# Blinds_Stepper.net
KiCad netlist of a schematic drawn in EAGLE
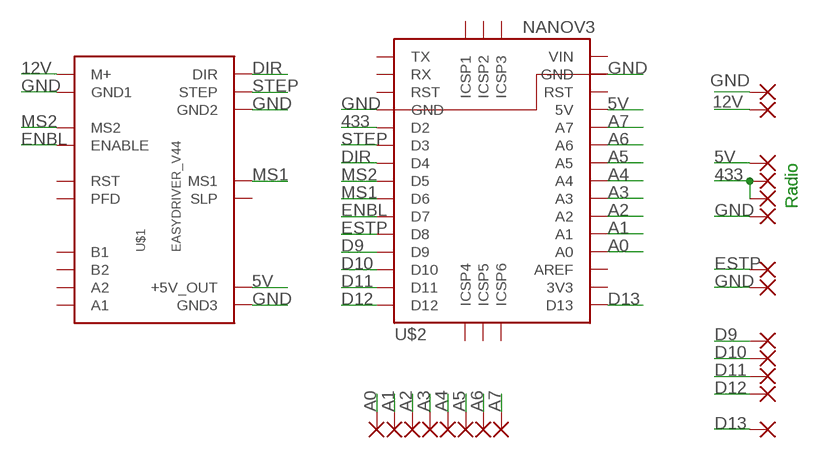
[diagram p0: schematic, sheet 1]

(export (version "E")
  (design (tool "Eeschema 10.0.6"))
  (components
    (comp (ref "+12")
      (value "1,6/0,8")
      (footprint "eagle-import:1,6_0,8")
      (libsource (lib "eagle-import") (part "1,6/0,8"))
    )
    (comp (ref "A0")
      (value "1,6/0,8")
      (footprint "eagle-import:1,6_0,8")
      (libsource (lib "eagle-import") (part "1,6/0,8"))
    )
    (comp (ref "A1")
      (value "1,6/0,8")
      (footprint "eagle-import:1,6_0,8")
      (libsource (lib "eagle-import") (part "1,6/0,8"))
    )
    (comp (ref "A2")
      (value "1,6/0,8")
      (footprint "eagle-import:1,6_0,8")
      (libsource (lib "eagle-import") (part "1,6/0,8"))
    )
    (comp (ref "A3")
      (value "1,6/0,8")
      (footprint "eagle-import:1,6_0,8")
      (libsource (lib "eagle-import") (part "1,6/0,8"))
    )
    (comp (ref "A4")
      (value "1,6/0,8")
      (footprint "eagle-import:1,6_0,8")
      (libsource (lib "eagle-import") (part "1,6/0,8"))
    )
    (comp (ref "A5")
      (value "1,6/0,8")
      (footprint "eagle-import:1,6_0,8")
      (libsource (lib "eagle-import") (part "1,6/0,8"))
    )
    (comp (ref "A6")
      (value "1,6/0,8")
      (footprint "eagle-import:1,6_0,8")
      (libsource (lib "eagle-import") (part "1,6/0,8"))
    )
    (comp (ref "A7")
      (value "1,6/0,8")
      (footprint "eagle-import:1,6_0,8")
      (libsource (lib "eagle-import") (part "1,6/0,8"))
    )
    (comp (ref "D1")
      (value "1,6/0,8")
      (footprint "eagle-import:1,6_0,8")
      (libsource (lib "eagle-import") (part "1,6/0,8"))
    )
    (comp (ref "D9")
      (value "1,6/0,8")
      (footprint "eagle-import:1,6_0,8")
      (libsource (lib "eagle-import") (part "1,6/0,8"))
    )
    (comp (ref "D10")
      (value "1,6/0,8")
      (footprint "eagle-import:1,6_0,8")
      (libsource (lib "eagle-import") (part "1,6/0,8"))
    )
    (comp (ref "D11")
      (value "1,6/0,8")
      (footprint "eagle-import:1,6_0,8")
      (libsource (lib "eagle-import") (part "1,6/0,8"))
    )
    (comp (ref "D12")
      (value "1,6/0,8")
      (footprint "eagle-import:1,6_0,8")
      (libsource (lib "eagle-import") (part "1,6/0,8"))
    )
    (comp (ref "END+")
      (value "1,6/0,8")
      (footprint "eagle-import:1,6_0,8")
      (libsource (lib "eagle-import") (part "1,6/0,8"))
    )
    (comp (ref "END-")
      (value "1,6/0,8")
      (footprint "eagle-import:1,6_0,8")
      (libsource (lib "eagle-import") (part "1,6/0,8"))
    )
    (comp (ref "GND")
      (value "1,6/0,8")
      (footprint "eagle-import:1,6_0,8")
      (libsource (lib "eagle-import") (part "1,6/0,8"))
    )
    (comp (ref "R+")
      (value "1,6/0,8")
      (footprint "eagle-import:1,6_0,8")
      (libsource (lib "eagle-import") (part "1,6/0,8"))
    )
    (comp (ref "R-")
      (value "1,6/0,8")
      (footprint "eagle-import:1,6_0,8")
      (libsource (lib "eagle-import") (part "1,6/0,8"))
    )
    (comp (ref "R1")
      (value "1,6/0,8")
      (footprint "eagle-import:1,6_0,8")
      (libsource (lib "eagle-import") (part "1,6/0,8"))
    )
    (comp (ref "R2")
      (value "1,6/0,8")
      (footprint "eagle-import:1,6_0,8")
      (libsource (lib "eagle-import") (part "1,6/0,8"))
    )
    (comp (ref "U$1")
      (value "EASYDRIVER_V44")
      (footprint "eagle-import:EASYDRIVER_V44")
      (libsource (lib "eagle-import") (part "EASYDRIVER_V44"))
    )
    (comp (ref "U$2")
      (value "NANOV3")
      (footprint "eagle-import:NANOV3")
      (libsource (lib "eagle-import") (part "NANOV3"))
    )
  )
  (nets
    (net (code "1") (name "/5V") (class "Default")
      (node (ref "R+") (pin "1") (pinfunction "P_1") (pintype "passive"))
      (node (ref "U$1") (pin "P$11") (pinfunction "+5V_OUT_P$11") (pintype "bidirectional"))
      (node (ref "U$2") (pin "5V") (pinfunction "5V_5V") (pintype "bidirectional"))
    )
    (net (code "2") (name "/12V") (class "Default")
      (node (ref "+12") (pin "1") (pinfunction "P_1") (pintype "passive"))
      (node (ref "U$1") (pin "M+") (pinfunction "M+_M+") (pintype "bidirectional"))
    )
    (net (code "3") (name "/433") (class "Default")
      (node (ref "R1") (pin "1") (pinfunction "P_1") (pintype "passive"))
      (node (ref "R2") (pin "1") (pinfunction "P_1") (pintype "passive"))
      (node (ref "U$2") (pin "D2") (pinfunction "D2_D2") (pintype "bidirectional"))
    )
    (net (code "4") (name "/A0") (class "Default")
      (node (ref "A0") (pin "1") (pinfunction "P_1") (pintype "passive"))
      (node (ref "U$2") (pin "A0") (pinfunction "A0_A0") (pintype "input"))
    )
    (net (code "5") (name "/A1") (class "Default")
      (node (ref "A1") (pin "1") (pinfunction "P_1") (pintype "passive"))
      (node (ref "U$2") (pin "A1") (pinfunction "A1_A1") (pintype "input"))
    )
    (net (code "6") (name "/A2") (class "Default")
      (node (ref "A2") (pin "1") (pinfunction "P_1") (pintype "passive"))
      (node (ref "U$2") (pin "A2") (pinfunction "A2_A2") (pintype "input"))
    )
    (net (code "7") (name "/A3") (class "Default")
      (node (ref "A3") (pin "1") (pinfunction "P_1") (pintype "passive"))
      (node (ref "U$2") (pin "A3") (pinfunction "A3_A3") (pintype "input"))
    )
    (net (code "8") (name "/A4") (class "Default")
      (node (ref "A4") (pin "1") (pinfunction "P_1") (pintype "passive"))
      (node (ref "U$2") (pin "A4") (pinfunction "A4_A4") (pintype "input"))
    )
    (net (code "9") (name "/A5") (class "Default")
      (node (ref "A5") (pin "1") (pinfunction "P_1") (pintype "passive"))
      (node (ref "U$2") (pin "A5") (pinfunction "A5_A5") (pintype "input"))
    )
    (net (code "10") (name "/A6") (class "Default")
      (node (ref "A6") (pin "1") (pinfunction "P_1") (pintype "passive"))
      (node (ref "U$2") (pin "A6") (pinfunction "A6_A6") (pintype "input"))
    )
    (net (code "11") (name "/A7") (class "Default")
      (node (ref "A7") (pin "1") (pinfunction "P_1") (pintype "passive"))
      (node (ref "U$2") (pin "A7") (pinfunction "A7_A7") (pintype "input"))
    )
    (net (code "12") (name "/D9") (class "Default")
      (node (ref "D9") (pin "1") (pinfunction "P_1") (pintype "passive"))
      (node (ref "U$2") (pin "D9") (pinfunction "D9_D9") (pintype "bidirectional"))
    )
    (net (code "13") (name "/D10") (class "Default")
      (node (ref "D10") (pin "1") (pinfunction "P_1") (pintype "passive"))
      (node (ref "U$2") (pin "D10") (pinfunction "D10_D10") (pintype "bidirectional"))
    )
    (net (code "14") (name "/D11") (class "Default")
      (node (ref "D11") (pin "1") (pinfunction "P_1") (pintype "passive"))
      (node (ref "U$2") (pin "D11") (pinfunction "D11_D11") (pintype "bidirectional"))
    )
    (net (code "15") (name "/D12") (class "Default")
      (node (ref "D12") (pin "1") (pinfunction "P_1") (pintype "passive"))
      (node (ref "U$2") (pin "D12") (pinfunction "D12_D12") (pintype "bidirectional"))
    )
    (net (code "16") (name "/D13") (class "Default")
      (node (ref "D1") (pin "1") (pinfunction "P_1") (pintype "passive"))
      (node (ref "U$2") (pin "D13") (pinfunction "D13_D13") (pintype "bidirectional"))
    )
    (net (code "17") (name "/DIR") (class "Default")
      (node (ref "U$1") (pin "DIR") (pinfunction "DIR_DIR") (pintype "bidirectional"))
      (node (ref "U$2") (pin "D4") (pinfunction "D4_D4") (pintype "bidirectional"))
    )
    (net (code "18") (name "/ENBL") (class "Default")
      (node (ref "U$1") (pin "ENABLE") (pinfunction "ENABLE_ENABLE") (pintype "bidirectional"))
      (node (ref "U$2") (pin "D7") (pinfunction "D7_D7") (pintype "bidirectional"))
    )
    (net (code "19") (name "/ESTP") (class "Default")
      (node (ref "END+") (pin "1") (pinfunction "P_1") (pintype "passive"))
      (node (ref "U$2") (pin "D8") (pinfunction "D8_D8") (pintype "bidirectional"))
    )
    (net (code "20") (name "/GND") (class "Default")
      (node (ref "END-") (pin "1") (pinfunction "P_1") (pintype "passive"))
      (node (ref "GND") (pin "1") (pinfunction "P_1") (pintype "passive"))
      (node (ref "R-") (pin "1") (pinfunction "P_1") (pintype "passive"))
      (node (ref "U$1") (pin "GND1") (pinfunction "GND1_GND1") (pintype "bidirectional"))
      (node (ref "U$1") (pin "GND2") (pinfunction "GND2_GND2") (pintype "bidirectional"))
      (node (ref "U$1") (pin "GND3") (pinfunction "GND3_GND3") (pintype "bidirectional"))
      (node (ref "U$2") (pin "GND1") (pinfunction "GND_GND1") (pintype "power_in"))
      (node (ref "U$2") (pin "GND2") (pinfunction "GND_GND2") (pintype "power_in"))
    )
    (net (code "21") (name "/MS1") (class "Default")
      (node (ref "U$1") (pin "MS1") (pinfunction "MS1_MS1") (pintype "bidirectional"))
      (node (ref "U$2") (pin "D6") (pinfunction "D6_D6") (pintype "bidirectional"))
    )
    (net (code "22") (name "/MS2") (class "Default")
      (node (ref "U$1") (pin "MS2") (pinfunction "MS2_MS2") (pintype "bidirectional"))
      (node (ref "U$2") (pin "D5") (pinfunction "D5_D5") (pintype "bidirectional"))
    )
    (net (code "23") (name "/STEP") (class "Default")
      (node (ref "U$1") (pin "STEP") (pinfunction "STEP_STEP") (pintype "bidirectional"))
      (node (ref "U$2") (pin "D3") (pinfunction "D3_D3") (pintype "bidirectional"))
    )
    (net (code "24") (name "/VIN") (class "Default")
      (node (ref "U$2") (pin "VIN") (pinfunction "VIN_VIN") (pintype "power_in"))
    )
    (net (code "25") (name "unconnected-(U$1-PadA1)") (class "Default")
      (node (ref "U$1") (pin "A1") (pinfunction "A1_A1") (pintype "bidirectional"))
    )
    (net (code "26") (name "unconnected-(U$1-PadA2)") (class "Default")
      (node (ref "U$1") (pin "A2") (pinfunction "A2_A2") (pintype "bidirectional"))
    )
    (net (code "27") (name "unconnected-(U$1-PadB1)") (class "Default")
      (node (ref "U$1") (pin "B1") (pinfunction "B1_B1") (pintype "bidirectional"))
    )
    (net (code "28") (name "unconnected-(U$1-PadB2)") (class "Default")
      (node (ref "U$1") (pin "B2") (pinfunction "B2_B2") (pintype "bidirectional"))
    )
    (net (code "29") (name "unconnected-(U$1-PadPFD)") (class "Default")
      (node (ref "U$1") (pin "PFD") (pinfunction "PFD_PFD") (pintype "bidirectional"))
    )
    (net (code "30") (name "unconnected-(U$1-PadRST)") (class "Default")
      (node (ref "U$1") (pin "RST") (pinfunction "RST_RST") (pintype "bidirectional"))
    )
    (net (code "31") (name "unconnected-(U$1-SLP-PadSLEEP)") (class "Default")
      (node (ref "U$1") (pin "SLEEP") (pinfunction "SLP_SLEEP") (pintype "bidirectional"))
    )
    (net (code "32") (name "unconnected-(U$2-ICSP1-PadP$34)") (class "Default")
      (node (ref "U$2") (pin "P$34") (pinfunction "ICSP1_P$34") (pintype "bidirectional"))
    )
    (net (code "33") (name "unconnected-(U$2-ICSP2-PadP$35)") (class "Default")
      (node (ref "U$2") (pin "P$35") (pinfunction "ICSP2_P$35") (pintype "bidirectional"))
    )
    (net (code "34") (name "unconnected-(U$2-ICSP3-PadP$36)") (class "Default")
      (node (ref "U$2") (pin "P$36") (pinfunction "ICSP3_P$36") (pintype "bidirectional"))
    )
    (net (code "35") (name "unconnected-(U$2-ICSP4-PadP$31)") (class "Default")
      (node (ref "U$2") (pin "P$31") (pinfunction "ICSP4_P$31") (pintype "bidirectional"))
    )
    (net (code "36") (name "unconnected-(U$2-ICSP5-PadP$32)") (class "Default")
      (node (ref "U$2") (pin "P$32") (pinfunction "ICSP5_P$32") (pintype "bidirectional"))
    )
    (net (code "37") (name "unconnected-(U$2-ICSP6-PadP$33)") (class "Default")
      (node (ref "U$2") (pin "P$33") (pinfunction "ICSP6_P$33") (pintype "bidirectional"))
    )
    (net (code "38") (name "unconnected-(U$2-Pad3V3)") (class "Default")
      (node (ref "U$2") (pin "3V3") (pinfunction "3V3_3V3") (pintype "output"))
    )
    (net (code "39") (name "unconnected-(U$2-PadAREF)") (class "Default")
      (node (ref "U$2") (pin "AREF") (pinfunction "AREF_AREF") (pintype "input"))
    )
    (net (code "40") (name "unconnected-(U$2-PadRX)") (class "Default")
      (node (ref "U$2") (pin "RX") (pinfunction "RX_RX") (pintype "bidirectional"))
    )
    (net (code "41") (name "unconnected-(U$2-PadTX)") (class "Default")
      (node (ref "U$2") (pin "TX") (pinfunction "TX_TX") (pintype "bidirectional"))
    )
    (net (code "42") (name "unconnected-(U$2-RST-PadRST1)") (class "Default")
      (node (ref "U$2") (pin "RST1") (pinfunction "RST_RST1") (pintype "input"))
    )
    (net (code "43") (name "unconnected-(U$2-RST-PadRST2)") (class "Default")
      (node (ref "U$2") (pin "RST2") (pinfunction "RST_RST2") (pintype "input"))
    )
  )
)
